# Sheet1.net
KiCad netlist of a schematic drawn in Altium Designer
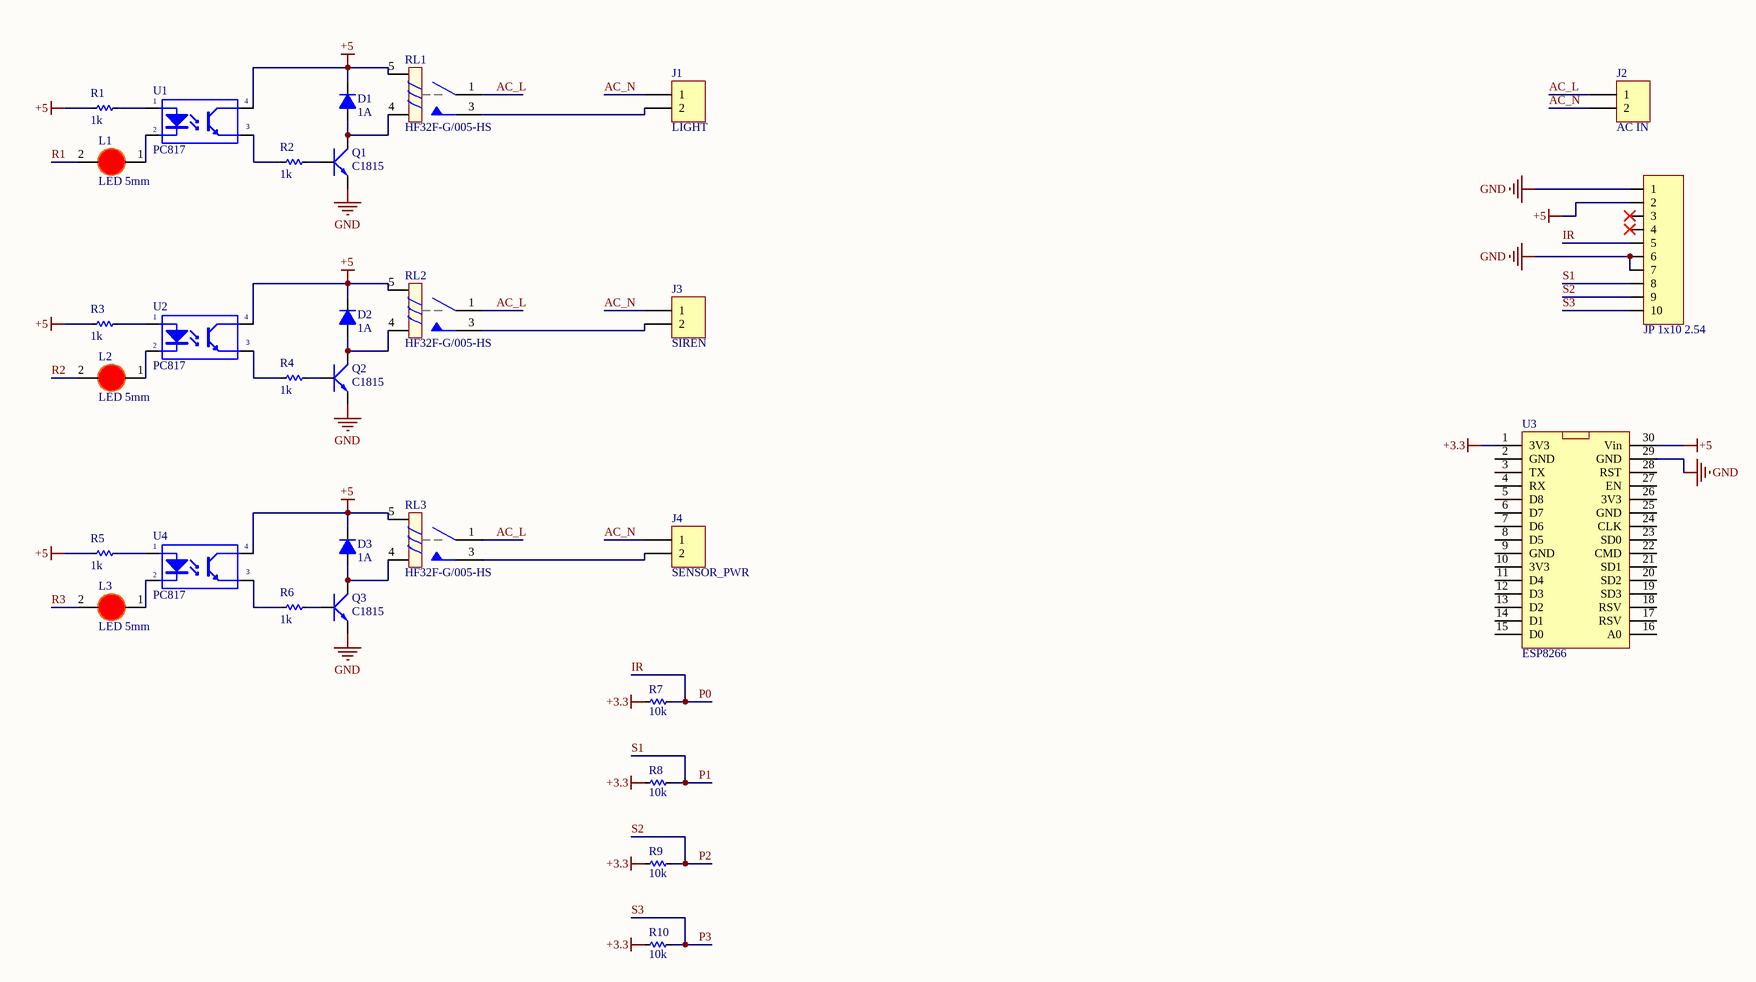
[diagram p0: Sheet1.SchDoc]

(export (version "E")
  (design (tool "Eeschema 10.0.6"))
  (components
    (comp (ref "D1")
      (value "1A")
      (footprint "DIODE 1A")
      (description "Cắm")
      (libsource (lib "Altium_Lib_by_KhueNguyenCreator") (part "Diode 1N4007"))
    )
    (comp (ref "D2")
      (value "1A")
      (footprint "DIODE 1A")
      (description "Cắm")
      (libsource (lib "Altium_Lib_by_KhueNguyenCreator") (part "Diode 1N4007"))
    )
    (comp (ref "D3")
      (value "1A")
      (footprint "DIODE 1A")
      (description "Cắm")
      (libsource (lib "Altium_Lib_by_KhueNguyenCreator") (part "Diode 1N4007"))
    )
    (comp (ref "J1")
      (value "LIGHT")
      (footprint "CON 2 2EDG5.08 B")
      (description "CON2 KF terminal")
      (libsource (lib "iuh-thuc-hanh") (part "CON 2 EDG5.08"))
    )
    (comp (ref "J2")
      (value "AC IN")
      (footprint "CON 2 2EDG5.08 B")
      (description "CON2 KF terminal")
      (libsource (lib "iuh-thuc-hanh") (part "CON 2 EDG5.08"))
    )
    (comp (ref "J3")
      (value "SIREN")
      (footprint "CON 2 2EDG5.08 B")
      (description "CON2 KF terminal")
      (libsource (lib "iuh-thuc-hanh") (part "CON 2 EDG5.08"))
    )
    (comp (ref "J4")
      (value "SENSOR_PWR")
      (footprint "CON 2 2EDG5.08 B")
      (description "CON2 KF terminal")
      (libsource (lib "iuh-thuc-hanh") (part "CON 2 EDG5.08"))
    )
    (comp (ref "JP1")
      (value "JP 1x10 2.54")
      (footprint "JP 1x10 CT")
      (description "Cắm")
      (libsource (lib "Altium_Lib_by_KhueNguyenCreator") (part "JP 1x10 2.54 Cai Thang"))
    )
    (comp (ref "L1")
      (value "LED 5mm")
      (footprint "LED-5MM-RED")
      (description "Cắm")
      (libsource (lib "Altium_Lib_by_KhueNguyenCreator") (part "LED 5mm Do"))
    )
    (comp (ref "L2")
      (value "LED 5mm")
      (footprint "LED-5MM-RED")
      (description "Cắm")
      (libsource (lib "Altium_Lib_by_KhueNguyenCreator") (part "LED 5mm Do"))
    )
    (comp (ref "L3")
      (value "LED 5mm")
      (footprint "LED-5MM-RED")
      (description "Cắm")
      (libsource (lib "Altium_Lib_by_KhueNguyenCreator") (part "LED 5mm Do"))
    )
    (comp (ref "Q1")
      (value "C1815")
      (footprint "TO92")
      (description "NPN transistor")
      (libsource (lib "Altium_Lib_by_KhueNguyenCreator") (part "Trans C1815 DIP"))
    )
    (comp (ref "Q2")
      (value "C1815")
      (footprint "TO92")
      (description "NPN transistor")
      (libsource (lib "Altium_Lib_by_KhueNguyenCreator") (part "Trans C1815 DIP"))
    )
    (comp (ref "Q3")
      (value "C1815")
      (footprint "TO92")
      (description "NPN transistor")
      (libsource (lib "Altium_Lib_by_KhueNguyenCreator") (part "Trans C1815 DIP"))
    )
    (comp (ref "R1")
      (value "1k")
      (footprint "RES-1/4W")
      (description "Res")
      (fields
        (field (name "MANUFACTURER") "Generic Components")
        (field (name "PUBLISHER") "Altium Hobart Technology Centre")
      )
      (libsource (lib "LIBRARY1") (part "Res"))
    )
    (comp (ref "R2")
      (value "1k")
      (footprint "RES-1/4W")
      (description "Res")
      (fields
        (field (name "MANUFACTURER") "Generic Components")
        (field (name "PUBLISHER") "Altium Hobart Technology Centre")
      )
      (libsource (lib "LIBRARY1") (part "Res"))
    )
    (comp (ref "R3")
      (value "1k")
      (footprint "RES-1/4W")
      (description "Res")
      (fields
        (field (name "MANUFACTURER") "Generic Components")
        (field (name "PUBLISHER") "Altium Hobart Technology Centre")
      )
      (libsource (lib "LIBRARY1") (part "Res"))
    )
    (comp (ref "R4")
      (value "1k")
      (footprint "RES-1/4W")
      (description "Res")
      (fields
        (field (name "MANUFACTURER") "Generic Components")
        (field (name "PUBLISHER") "Altium Hobart Technology Centre")
      )
      (libsource (lib "LIBRARY1") (part "Res"))
    )
    (comp (ref "R5")
      (value "1k")
      (footprint "RES-1/4W")
      (description "Res")
      (fields
        (field (name "MANUFACTURER") "Generic Components")
        (field (name "PUBLISHER") "Altium Hobart Technology Centre")
      )
      (libsource (lib "LIBRARY1") (part "Res"))
    )
    (comp (ref "R6")
      (value "1k")
      (footprint "RES-1/4W")
      (description "Res")
      (fields
        (field (name "MANUFACTURER") "Generic Components")
        (field (name "PUBLISHER") "Altium Hobart Technology Centre")
      )
      (libsource (lib "LIBRARY1") (part "Res"))
    )
    (comp (ref "R7")
      (value "10k")
      (footprint "RES-1/4W")
      (description "Res")
      (fields
        (field (name "MANUFACTURER") "Generic Components")
        (field (name "PUBLISHER") "Altium Hobart Technology Centre")
      )
      (libsource (lib "LIBRARY1") (part "Res"))
    )
    (comp (ref "R8")
      (value "10k")
      (footprint "RES-1/4W")
      (description "Res")
      (fields
        (field (name "MANUFACTURER") "Generic Components")
        (field (name "PUBLISHER") "Altium Hobart Technology Centre")
      )
      (libsource (lib "LIBRARY1") (part "Res"))
    )
    (comp (ref "R9")
      (value "10k")
      (footprint "RES-1/4W")
      (description "Res")
      (fields
        (field (name "MANUFACTURER") "Generic Components")
        (field (name "PUBLISHER") "Altium Hobart Technology Centre")
      )
      (libsource (lib "LIBRARY1") (part "Res"))
    )
    (comp (ref "R10")
      (value "10k")
      (footprint "RES-1/4W")
      (description "Res")
      (fields
        (field (name "MANUFACTURER") "Generic Components")
        (field (name "PUBLISHER") "Altium Hobart Technology Centre")
      )
      (libsource (lib "LIBRARY1") (part "Res"))
    )
    (comp (ref "RL1")
      (value "HF32F-G/005-HS")
      (footprint "HF32F-G")
      (description "Relay hongfa 10A 4P HF32F-G/005-HS")
      (libsource (lib "iuh-thuc-hanh") (part "Relay HF 10A"))
    )
    (comp (ref "RL2")
      (value "HF32F-G/005-HS")
      (footprint "HF32F-G")
      (description "Relay hongfa 10A 4P HF32F-G/005-HS")
      (libsource (lib "iuh-thuc-hanh") (part "Relay HF 10A"))
    )
    (comp (ref "RL3")
      (value "HF32F-G/005-HS")
      (footprint "HF32F-G")
      (description "Relay hongfa 10A 4P HF32F-G/005-HS")
      (libsource (lib "iuh-thuc-hanh") (part "Relay HF 10A"))
    )
    (comp (ref "U1")
      (value "PC817")
      (footprint "DIP4")
      (description "Single Opto")
      (libsource (lib "LIBRARY1") (part "PC817"))
    )
    (comp (ref "U2")
      (value "PC817")
      (footprint "DIP4")
      (description "Single Opto")
      (libsource (lib "LIBRARY1") (part "PC817"))
    )
    (comp (ref "U3")
      (value "ESP8266")
      (footprint "NODE MCU CH340")
      (description "ESP8266 nodemcu 1.0")
      (libsource (lib "iuh-thuc-hanh") (part "NODEMCU 1.0"))
    )
    (comp (ref "U4")
      (value "PC817")
      (footprint "DIP4")
      (description "Single Opto")
      (libsource (lib "LIBRARY1") (part "PC817"))
    )
  )
  (nets
    (net (code "1") (name "+3.3") (class "Default")
      (node (ref "R10") (pin "2") (pinfunction "2_2") (pintype "passive"))
      (node (ref "R7") (pin "2") (pinfunction "2_2") (pintype "passive"))
      (node (ref "R8") (pin "2") (pinfunction "2_2") (pintype "passive"))
      (node (ref "R9") (pin "2") (pinfunction "2_2") (pintype "passive"))
      (node (ref "U3") (pin "1") (pinfunction "3V3_1") (pintype "passive"))
    )
    (net (code "2") (name "+5") (class "Default")
      (node (ref "D1") (pin "2") (pinfunction "K_2") (pintype "passive"))
      (node (ref "D2") (pin "2") (pinfunction "K_2") (pintype "passive"))
      (node (ref "D3") (pin "2") (pinfunction "K_2") (pintype "passive"))
      (node (ref "JP1") (pin "2") (pinfunction "2_2") (pintype "passive"))
      (node (ref "R1") (pin "1") (pinfunction "1_1") (pintype "passive"))
      (node (ref "R3") (pin "1") (pinfunction "1_1") (pintype "passive"))
      (node (ref "R5") (pin "1") (pinfunction "1_1") (pintype "passive"))
      (node (ref "RL1") (pin "5") (pinfunction "5_5") (pintype "passive"))
      (node (ref "RL2") (pin "5") (pinfunction "5_5") (pintype "passive"))
      (node (ref "RL3") (pin "5") (pinfunction "5_5") (pintype "passive"))
      (node (ref "U1") (pin "4") (pinfunction "C_4") (pintype "passive"))
      (node (ref "U2") (pin "4") (pinfunction "C_4") (pintype "passive"))
      (node (ref "U3") (pin "30") (pinfunction "Vin_30") (pintype "passive"))
      (node (ref "U4") (pin "4") (pinfunction "C_4") (pintype "passive"))
    )
    (net (code "3") (name "/AC_L") (class "Default")
      (node (ref "J2") (pin "1") (pinfunction "1_1") (pintype "passive"))
      (node (ref "RL1") (pin "1") (pinfunction "1_1") (pintype "passive"))
      (node (ref "RL2") (pin "1") (pinfunction "1_1") (pintype "passive"))
      (node (ref "RL3") (pin "1") (pinfunction "1_1") (pintype "passive"))
    )
    (net (code "4") (name "/AC_N") (class "Default")
      (node (ref "J1") (pin "1") (pinfunction "1_1") (pintype "passive"))
      (node (ref "J2") (pin "2") (pinfunction "2_2") (pintype "passive"))
      (node (ref "J3") (pin "1") (pinfunction "1_1") (pintype "passive"))
      (node (ref "J4") (pin "1") (pinfunction "1_1") (pintype "passive"))
    )
    (net (code "5") (name "/IR") (class "Default")
      (node (ref "JP1") (pin "5") (pinfunction "5_5") (pintype "passive"))
      (node (ref "R7") (pin "1") (pinfunction "1_1") (pintype "passive"))
    )
    (net (code "6") (name "/P1") (class "Default")
      (node (ref "JP1") (pin "8") (pinfunction "8_8") (pintype "passive"))
      (node (ref "R8") (pin "1") (pinfunction "1_1") (pintype "passive"))
    )
    (net (code "7") (name "/P2") (class "Default")
      (node (ref "JP1") (pin "9") (pinfunction "9_9") (pintype "passive"))
      (node (ref "R9") (pin "1") (pinfunction "1_1") (pintype "passive"))
    )
    (net (code "8") (name "/P3") (class "Default")
      (node (ref "JP1") (pin "10") (pinfunction "10_10") (pintype "passive"))
      (node (ref "R10") (pin "1") (pinfunction "1_1") (pintype "passive"))
    )
    (net (code "9") (name "/R1") (class "Default")
      (node (ref "L1") (pin "2") (pinfunction "K_2") (pintype "passive"))
    )
    (net (code "10") (name "/R2") (class "Default")
      (node (ref "L2") (pin "2") (pinfunction "K_2") (pintype "passive"))
    )
    (net (code "11") (name "/R3") (class "Default")
      (node (ref "L3") (pin "2") (pinfunction "K_2") (pintype "passive"))
    )
    (net (code "12") (name "GND") (class "Default")
      (node (ref "JP1") (pin "1") (pinfunction "1_1") (pintype "passive"))
      (node (ref "JP1") (pin "6") (pinfunction "6_6") (pintype "passive"))
      (node (ref "JP1") (pin "7") (pinfunction "7_7") (pintype "passive"))
      (node (ref "Q1") (pin "1") (pinfunction "E_1") (pintype "passive"))
      (node (ref "Q2") (pin "1") (pinfunction "E_1") (pintype "passive"))
      (node (ref "Q3") (pin "1") (pinfunction "E_1") (pintype "passive"))
      (node (ref "U3") (pin "29") (pinfunction "GND_29") (pintype "passive"))
    )
    (net (code "13") (name "Net-(D1-A)") (class "Default")
      (node (ref "D1") (pin "1") (pinfunction "A_1") (pintype "passive"))
      (node (ref "Q1") (pin "2") (pinfunction "C_2") (pintype "passive"))
      (node (ref "RL1") (pin "4") (pinfunction "4_4") (pintype "passive"))
    )
    (net (code "14") (name "Net-(D2-A)") (class "Default")
      (node (ref "D2") (pin "1") (pinfunction "A_1") (pintype "passive"))
      (node (ref "Q2") (pin "2") (pinfunction "C_2") (pintype "passive"))
      (node (ref "RL2") (pin "4") (pinfunction "4_4") (pintype "passive"))
    )
    (net (code "15") (name "Net-(D3-A)") (class "Default")
      (node (ref "D3") (pin "1") (pinfunction "A_1") (pintype "passive"))
      (node (ref "Q3") (pin "2") (pinfunction "C_2") (pintype "passive"))
      (node (ref "RL3") (pin "4") (pinfunction "4_4") (pintype "passive"))
    )
    (net (code "16") (name "Net-(J1-Pad2)") (class "Default")
      (node (ref "J1") (pin "2") (pinfunction "2_2") (pintype "passive"))
      (node (ref "RL1") (pin "3") (pinfunction "3_3") (pintype "passive"))
    )
    (net (code "17") (name "Net-(J3-Pad2)") (class "Default")
      (node (ref "J3") (pin "2") (pinfunction "2_2") (pintype "passive"))
      (node (ref "RL2") (pin "3") (pinfunction "3_3") (pintype "passive"))
    )
    (net (code "18") (name "Net-(J4-Pad2)") (class "Default")
      (node (ref "J4") (pin "2") (pinfunction "2_2") (pintype "passive"))
      (node (ref "RL3") (pin "3") (pinfunction "3_3") (pintype "passive"))
    )
    (net (code "19") (name "Net-(L1-A)") (class "Default")
      (node (ref "L1") (pin "1") (pinfunction "A_1") (pintype "passive"))
      (node (ref "U1") (pin "2") (pinfunction "K_2") (pintype "passive"))
    )
    (net (code "20") (name "Net-(L2-A)") (class "Default")
      (node (ref "L2") (pin "1") (pinfunction "A_1") (pintype "passive"))
      (node (ref "U2") (pin "2") (pinfunction "K_2") (pintype "passive"))
    )
    (net (code "21") (name "Net-(L3-A)") (class "Default")
      (node (ref "L3") (pin "1") (pinfunction "A_1") (pintype "passive"))
      (node (ref "U4") (pin "2") (pinfunction "K_2") (pintype "passive"))
    )
    (net (code "22") (name "Net-(Q1-B)") (class "Default")
      (node (ref "Q1") (pin "3") (pinfunction "B_3") (pintype "passive"))
      (node (ref "R2") (pin "2") (pinfunction "2_2") (pintype "passive"))
    )
    (net (code "23") (name "Net-(Q2-B)") (class "Default")
      (node (ref "Q2") (pin "3") (pinfunction "B_3") (pintype "passive"))
      (node (ref "R4") (pin "2") (pinfunction "2_2") (pintype "passive"))
    )
    (net (code "24") (name "Net-(Q3-B)") (class "Default")
      (node (ref "Q3") (pin "3") (pinfunction "B_3") (pintype "passive"))
      (node (ref "R6") (pin "2") (pinfunction "2_2") (pintype "passive"))
    )
    (net (code "25") (name "Net-(U1-A)") (class "Default")
      (node (ref "R1") (pin "2") (pinfunction "2_2") (pintype "passive"))
      (node (ref "U1") (pin "1") (pinfunction "A_1") (pintype "passive"))
    )
    (net (code "26") (name "Net-(U1-E)") (class "Default")
      (node (ref "R2") (pin "1") (pinfunction "1_1") (pintype "passive"))
      (node (ref "U1") (pin "3") (pinfunction "E_3") (pintype "passive"))
    )
    (net (code "27") (name "Net-(U2-A)") (class "Default")
      (node (ref "R3") (pin "2") (pinfunction "2_2") (pintype "passive"))
      (node (ref "U2") (pin "1") (pinfunction "A_1") (pintype "passive"))
    )
    (net (code "28") (name "Net-(U2-E)") (class "Default")
      (node (ref "R4") (pin "1") (pinfunction "1_1") (pintype "passive"))
      (node (ref "U2") (pin "3") (pinfunction "E_3") (pintype "passive"))
    )
    (net (code "29") (name "Net-(U4-A)") (class "Default")
      (node (ref "R5") (pin "2") (pinfunction "2_2") (pintype "passive"))
      (node (ref "U4") (pin "1") (pinfunction "A_1") (pintype "passive"))
    )
    (net (code "30") (name "Net-(U4-E)") (class "Default")
      (node (ref "R6") (pin "1") (pinfunction "1_1") (pintype "passive"))
      (node (ref "U4") (pin "3") (pinfunction "E_3") (pintype "passive"))
    )
    (net (code "31") (name "unconnected-(JP1-Pad3)") (class "Default")
      (node (ref "JP1") (pin "3") (pinfunction "3_3") (pintype "passive+no_connect"))
    )
    (net (code "32") (name "unconnected-(JP1-Pad4)") (class "Default")
      (node (ref "JP1") (pin "4") (pinfunction "4_4") (pintype "passive+no_connect"))
    )
    (net (code "33") (name "unconnected-(U3-3V3-Pad10)") (class "Default")
      (node (ref "U3") (pin "10") (pinfunction "3V3_10") (pintype "passive"))
    )
    (net (code "34") (name "unconnected-(U3-3V3-Pad26)") (class "Default")
      (node (ref "U3") (pin "26") (pinfunction "3V3_26") (pintype "passive"))
    )
    (net (code "35") (name "unconnected-(U3-A0-Pad16)") (class "Default")
      (node (ref "U3") (pin "16") (pinfunction "A0_16") (pintype "passive"))
    )
    (net (code "36") (name "unconnected-(U3-CLK-Pad24)") (class "Default")
      (node (ref "U3") (pin "24") (pinfunction "CLK_24") (pintype "passive"))
    )
    (net (code "37") (name "unconnected-(U3-CMD-Pad22)") (class "Default")
      (node (ref "U3") (pin "22") (pinfunction "CMD_22") (pintype "passive"))
    )
    (net (code "38") (name "unconnected-(U3-D0-Pad15)") (class "Default")
      (node (ref "U3") (pin "15") (pinfunction "D0_15") (pintype "passive"))
    )
    (net (code "39") (name "unconnected-(U3-D1-Pad14)") (class "Default")
      (node (ref "U3") (pin "14") (pinfunction "D1_14") (pintype "passive"))
    )
    (net (code "40") (name "unconnected-(U3-D2-Pad13)") (class "Default")
      (node (ref "U3") (pin "13") (pinfunction "D2_13") (pintype "passive"))
    )
    (net (code "41") (name "unconnected-(U3-D3-Pad12)") (class "Default")
      (node (ref "U3") (pin "12") (pinfunction "D3_12") (pintype "passive"))
    )
    (net (code "42") (name "unconnected-(U3-D4-Pad11)") (class "Default")
      (node (ref "U3") (pin "11") (pinfunction "D4_11") (pintype "passive"))
    )
    (net (code "43") (name "unconnected-(U3-D5-Pad8)") (class "Default")
      (node (ref "U3") (pin "8") (pinfunction "D5_8") (pintype "passive"))
    )
    (net (code "44") (name "unconnected-(U3-D6-Pad7)") (class "Default")
      (node (ref "U3") (pin "7") (pinfunction "D6_7") (pintype "passive"))
    )
    (net (code "45") (name "unconnected-(U3-D7-Pad6)") (class "Default")
      (node (ref "U3") (pin "6") (pinfunction "D7_6") (pintype "passive"))
    )
    (net (code "46") (name "unconnected-(U3-D8-Pad5)") (class "Default")
      (node (ref "U3") (pin "5") (pinfunction "D8_5") (pintype "passive"))
    )
    (net (code "47") (name "unconnected-(U3-EN-Pad27)") (class "Default")
      (node (ref "U3") (pin "27") (pinfunction "EN_27") (pintype "passive"))
    )
    (net (code "48") (name "unconnected-(U3-GND-Pad2)") (class "Default")
      (node (ref "U3") (pin "2") (pinfunction "GND_2") (pintype "passive"))
    )
    (net (code "49") (name "unconnected-(U3-GND-Pad9)") (class "Default")
      (node (ref "U3") (pin "9") (pinfunction "GND_9") (pintype "passive"))
    )
    (net (code "50") (name "unconnected-(U3-GND-Pad25)") (class "Default")
      (node (ref "U3") (pin "25") (pinfunction "GND_25") (pintype "passive"))
    )
    (net (code "51") (name "unconnected-(U3-RST-Pad28)") (class "Default")
      (node (ref "U3") (pin "28") (pinfunction "RST_28") (pintype "passive"))
    )
    (net (code "52") (name "unconnected-(U3-RSV-Pad17)") (class "Default")
      (node (ref "U3") (pin "17") (pinfunction "RSV_17") (pintype "passive"))
    )
    (net (code "53") (name "unconnected-(U3-RSV-Pad18)") (class "Default")
      (node (ref "U3") (pin "18") (pinfunction "RSV_18") (pintype "passive"))
    )
    (net (code "54") (name "unconnected-(U3-RX-Pad4)") (class "Default")
      (node (ref "U3") (pin "4") (pinfunction "RX_4") (pintype "passive"))
    )
    (net (code "55") (name "unconnected-(U3-SD0-Pad23)") (class "Default")
      (node (ref "U3") (pin "23") (pinfunction "SD0_23") (pintype "passive"))
    )
    (net (code "56") (name "unconnected-(U3-SD1-Pad21)") (class "Default")
      (node (ref "U3") (pin "21") (pinfunction "SD1_21") (pintype "passive"))
    )
    (net (code "57") (name "unconnected-(U3-SD2-Pad20)") (class "Default")
      (node (ref "U3") (pin "20") (pinfunction "SD2_20") (pintype "passive"))
    )
    (net (code "58") (name "unconnected-(U3-SD3-Pad19)") (class "Default")
      (node (ref "U3") (pin "19") (pinfunction "SD3_19") (pintype "passive"))
    )
    (net (code "59") (name "unconnected-(U3-TX-Pad3)") (class "Default")
      (node (ref "U3") (pin "3") (pinfunction "TX_3") (pintype "passive"))
    )
  )
)
